# MultiDrop.net
KiCad netlist of a schematic drawn in EAGLE
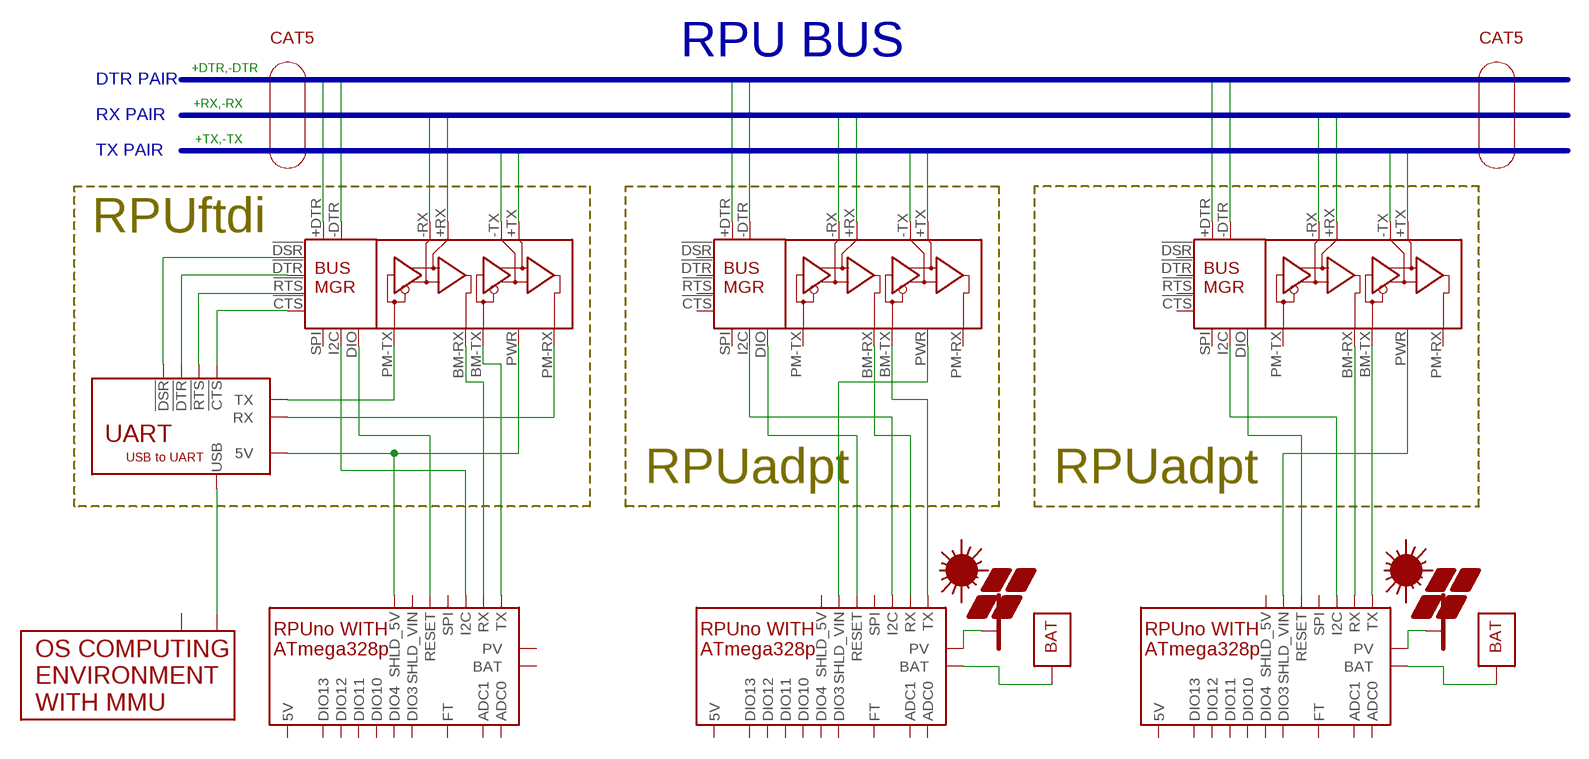
[diagram p0: schematic, sheet 1]

(export (version "E")
  (design (tool "Eeschema 10.0.6"))
  (components
    (comp (ref "BM1")
      (value "RPUNO")
      (footprint "eagle-import:NA-20")
      (libsource (lib "eagle-import") (part "RPUNO"))
    )
    (comp (ref "BM2")
      (value "RPUNO")
      (footprint "eagle-import:NA-20")
      (libsource (lib "eagle-import") (part "RPUNO"))
    )
    (comp (ref "BM3")
      (value "RPUNO")
      (footprint "eagle-import:NA-20")
      (libsource (lib "eagle-import") (part "RPUNO"))
    )
    (comp (ref "PM2")
      (value "TRUSTWORTHY")
      (footprint "eagle-import:NA-20")
      (libsource (lib "eagle-import") (part "TRUSTWORTHY"))
    )
    (comp (ref "PV2")
      (value "PV")
      (footprint "eagle-import:NA-20")
      (libsource (lib "eagle-import") (part "PV"))
    )
    (comp (ref "PV4")
      (value "PV")
      (footprint "eagle-import:NA-20")
      (libsource (lib "eagle-import") (part "PV"))
    )
    (comp (ref "U$1")
      (value "BUS_MGR")
      (footprint "eagle-import:NA-10_WITH_RPU_NAMES")
      (libsource (lib "eagle-import") (part "BUS_MGR"))
    )
    (comp (ref "U$2")
      (value "BUS_MGR")
      (footprint "eagle-import:NA-10_WITH_RPU_NAMES")
      (libsource (lib "eagle-import") (part "BUS_MGR"))
    )
    (comp (ref "U$5")
      (value "BUS_MGR")
      (footprint "eagle-import:NA-10_WITH_RPU_NAMES")
      (libsource (lib "eagle-import") (part "BUS_MGR"))
    )
    (comp (ref "U$7")
      (value "BAT")
      (footprint "eagle-import:NA-20")
      (libsource (lib "eagle-import") (part "BAT"))
    )
    (comp (ref "U$9")
      (value "BAT")
      (footprint "eagle-import:NA-20")
      (libsource (lib "eagle-import") (part "BAT"))
    )
    (comp (ref "UART1")
      (value "UART")
      (footprint "eagle-import:NA-20")
      (libsource (lib "eagle-import") (part "UART"))
    )
  )
  (nets
    (net (code "10") (name "Net-(BM1-BAT)") (class "Default")
      (node (ref "BM1") (pin "9") (pinfunction "BAT_9") (pintype "bidirectional"))
      (node (ref "U$9") (pin "1") (pinfunction "BAT_PWR_1") (pintype "bidirectional"))
    )
    (net (code "11") (name "Net-(BM1-I2C)") (class "Default")
      (node (ref "BM1") (pin "3") (pinfunction "I2C_3") (pintype "bidirectional"))
      (node (ref "U$2") (pin "I2C") (pinfunction "I2C_I2C") (pintype "bidirectional"))
    )
    (net (code "12") (name "Net-(BM1-PV)") (class "Default")
      (node (ref "BM1") (pin "8") (pinfunction "PV_8") (pintype "bidirectional"))
      (node (ref "PV2") (pin "1") (pinfunction "PV_PWR_1") (pintype "bidirectional"))
    )
    (net (code "13") (name "Net-(BM1-RESET)") (class "Default")
      (node (ref "BM1") (pin "5") (pinfunction "RESET_5") (pintype "bidirectional"))
      (node (ref "U$2") (pin "DIO") (pinfunction "DIO_DIO") (pintype "bidirectional"))
    )
    (net (code "14") (name "Net-(BM1-RX)") (class "Default")
      (node (ref "BM1") (pin "2") (pinfunction "RX_2") (pintype "bidirectional"))
      (node (ref "U$2") (pin "BM-RX") (pinfunction "BM_RX_BM-RX") (pintype "bidirectional"))
    )
    (net (code "15") (name "Net-(BM1-SHLD_VIN)") (class "Default")
      (node (ref "BM1") (pin "7") (pinfunction "SHLD_VIN_7") (pintype "bidirectional"))
      (node (ref "U$2") (pin "PWR") (pinfunction "PWR_PWR") (pintype "bidirectional"))
    )
    (net (code "16") (name "Net-(BM1-TX)") (class "Default")
      (node (ref "BM1") (pin "1") (pinfunction "TX_1") (pintype "bidirectional"))
      (node (ref "U$2") (pin "BM-TX") (pinfunction "BM_TX_BM-TX") (pintype "bidirectional"))
    )
    (net (code "17") (name "Net-(BM2-I2C)") (class "Default")
      (node (ref "BM2") (pin "3") (pinfunction "I2C_3") (pintype "bidirectional"))
      (node (ref "U$1") (pin "I2C") (pinfunction "I2C_I2C") (pintype "bidirectional"))
    )
    (net (code "18") (name "Net-(BM2-RESET)") (class "Default")
      (node (ref "BM2") (pin "5") (pinfunction "RESET_5") (pintype "bidirectional"))
      (node (ref "U$1") (pin "DIO") (pinfunction "DIO_DIO") (pintype "bidirectional"))
    )
    (net (code "19") (name "Net-(BM2-RX)") (class "Default")
      (node (ref "BM2") (pin "2") (pinfunction "RX_2") (pintype "bidirectional"))
      (node (ref "U$1") (pin "BM-RX") (pinfunction "BM_RX_BM-RX") (pintype "bidirectional"))
    )
    (net (code "20") (name "Net-(BM2-SHLD_5V)") (class "Default")
      (node (ref "BM2") (pin "6") (pinfunction "SHLD_5V_6") (pintype "bidirectional"))
      (node (ref "U$1") (pin "PWR") (pinfunction "PWR_PWR") (pintype "bidirectional"))
      (node (ref "UART1") (pin "8") (pinfunction "5V_8") (pintype "bidirectional"))
    )
    (net (code "21") (name "Net-(BM2-TX)") (class "Default")
      (node (ref "BM2") (pin "1") (pinfunction "TX_1") (pintype "bidirectional"))
      (node (ref "U$1") (pin "BM-TX") (pinfunction "BM_TX_BM-TX") (pintype "bidirectional"))
    )
    (net (code "22") (name "Net-(BM3-BAT)") (class "Default")
      (node (ref "BM3") (pin "9") (pinfunction "BAT_9") (pintype "bidirectional"))
      (node (ref "U$7") (pin "1") (pinfunction "BAT_PWR_1") (pintype "bidirectional"))
    )
    (net (code "23") (name "Net-(BM3-I2C)") (class "Default")
      (node (ref "BM3") (pin "3") (pinfunction "I2C_3") (pintype "bidirectional"))
      (node (ref "U$5") (pin "I2C") (pinfunction "I2C_I2C") (pintype "bidirectional"))
    )
    (net (code "24") (name "Net-(BM3-PV)") (class "Default")
      (node (ref "BM3") (pin "8") (pinfunction "PV_8") (pintype "bidirectional"))
      (node (ref "PV4") (pin "1") (pinfunction "PV_PWR_1") (pintype "bidirectional"))
    )
    (net (code "25") (name "Net-(BM3-RESET)") (class "Default")
      (node (ref "BM3") (pin "5") (pinfunction "RESET_5") (pintype "bidirectional"))
      (node (ref "U$5") (pin "DIO") (pinfunction "DIO_DIO") (pintype "bidirectional"))
    )
    (net (code "26") (name "Net-(BM3-RX)") (class "Default")
      (node (ref "BM3") (pin "2") (pinfunction "RX_2") (pintype "bidirectional"))
      (node (ref "U$5") (pin "BM-RX") (pinfunction "BM_RX_BM-RX") (pintype "bidirectional"))
    )
    (net (code "27") (name "Net-(BM3-SHLD_VIN)") (class "Default")
      (node (ref "BM3") (pin "7") (pinfunction "SHLD_VIN_7") (pintype "bidirectional"))
      (node (ref "U$5") (pin "PWR") (pinfunction "PWR_PWR") (pintype "bidirectional"))
    )
    (net (code "28") (name "Net-(BM3-TX)") (class "Default")
      (node (ref "BM3") (pin "1") (pinfunction "TX_1") (pintype "bidirectional"))
      (node (ref "U$5") (pin "BM-TX") (pinfunction "BM_TX_BM-TX") (pintype "bidirectional"))
    )
    (net (code "29") (name "Net-(PM2-TX)") (class "Default")
      (node (ref "PM2") (pin "2") (pinfunction "TX_2") (pintype "bidirectional"))
      (node (ref "UART1") (pin "7") (pinfunction "USB_7") (pintype "bidirectional"))
    )
    (net (code "30") (name "Net-(U$1-PM_RX)") (class "Default")
      (node (ref "U$1") (pin "PM-RX") (pinfunction "PM_RX_PM-RX") (pintype "bidirectional"))
      (node (ref "UART1") (pin "5") (pinfunction "RX_5") (pintype "bidirectional"))
    )
    (net (code "31") (name "Net-(U$1-PM_TX)") (class "Default")
      (node (ref "U$1") (pin "PM-TX") (pinfunction "PM_TX_PM-TX") (pintype "bidirectional"))
      (node (ref "UART1") (pin "6") (pinfunction "TX_6") (pintype "bidirectional"))
    )
    (net (code "32") (name "Net-(U$1-~{CTS})") (class "Default")
      (node (ref "U$1") (pin "!CTS") (pinfunction "~{CTS}_!CTS") (pintype "bidirectional"))
      (node (ref "UART1") (pin "1") (pinfunction "~{CTS}_1") (pintype "input"))
    )
    (net (code "33") (name "Net-(U$1-~{DSR})") (class "Default")
      (node (ref "U$1") (pin "!DSR") (pinfunction "~{DSR}_!DSR") (pintype "bidirectional"))
      (node (ref "UART1") (pin "2") (pinfunction "~{DSR}_2") (pintype "input"))
    )
    (net (code "34") (name "Net-(U$1-~{DTR})") (class "Default")
      (node (ref "U$1") (pin "!DTR") (pinfunction "~{DTR}_!DTR") (pintype "bidirectional"))
      (node (ref "UART1") (pin "3") (pinfunction "~{DTR}_3") (pintype "output"))
    )
    (net (code "35") (name "Net-(U$1-~{RTS})") (class "Default")
      (node (ref "U$1") (pin "!RTS") (pinfunction "~{RTS}_!RTS") (pintype "bidirectional"))
      (node (ref "UART1") (pin "4") (pinfunction "~{RTS}_4") (pintype "output"))
    )
    (net (code "36") (name "unconnected-(BM1-5V-Pad19)") (class "Default")
      (node (ref "BM1") (pin "19") (pinfunction "5V_19") (pintype "bidirectional"))
    )
    (net (code "37") (name "unconnected-(BM1-ADC0-Pad10)") (class "Default")
      (node (ref "BM1") (pin "10") (pinfunction "ADC0_10") (pintype "bidirectional"))
    )
    (net (code "38") (name "unconnected-(BM1-ADC1-Pad11)") (class "Default")
      (node (ref "BM1") (pin "11") (pinfunction "ADC1_11") (pintype "bidirectional"))
    )
    (net (code "39") (name "unconnected-(BM1-DIO3-Pad13)") (class "Default")
      (node (ref "BM1") (pin "13") (pinfunction "DIO3_13") (pintype "bidirectional"))
    )
    (net (code "40") (name "unconnected-(BM1-DIO4-Pad14)") (class "Default")
      (node (ref "BM1") (pin "14") (pinfunction "DIO4_14") (pintype "bidirectional"))
    )
    (net (code "41") (name "unconnected-(BM1-DIO10-Pad15)") (class "Default")
      (node (ref "BM1") (pin "15") (pinfunction "DIO10_15") (pintype "bidirectional"))
    )
    (net (code "42") (name "unconnected-(BM1-DIO11-Pad16)") (class "Default")
      (node (ref "BM1") (pin "16") (pinfunction "DIO11_16") (pintype "bidirectional"))
    )
    (net (code "43") (name "unconnected-(BM1-DIO12-Pad17)") (class "Default")
      (node (ref "BM1") (pin "17") (pinfunction "DIO12_17") (pintype "bidirectional"))
    )
    (net (code "44") (name "unconnected-(BM1-DIO13-Pad18)") (class "Default")
      (node (ref "BM1") (pin "18") (pinfunction "DIO13_18") (pintype "bidirectional"))
    )
    (net (code "45") (name "unconnected-(BM1-FT-Pad12)") (class "Default")
      (node (ref "BM1") (pin "12") (pinfunction "FT_12") (pintype "bidirectional"))
    )
    (net (code "46") (name "unconnected-(BM1-SHLD_5V-Pad6)") (class "Default")
      (node (ref "BM1") (pin "6") (pinfunction "SHLD_5V_6") (pintype "bidirectional"))
    )
    (net (code "47") (name "unconnected-(BM1-SPI-Pad4)") (class "Default")
      (node (ref "BM1") (pin "4") (pinfunction "SPI_4") (pintype "bidirectional"))
    )
    (net (code "48") (name "unconnected-(BM2-5V-Pad19)") (class "Default")
      (node (ref "BM2") (pin "19") (pinfunction "5V_19") (pintype "bidirectional"))
    )
    (net (code "49") (name "unconnected-(BM2-ADC0-Pad10)") (class "Default")
      (node (ref "BM2") (pin "10") (pinfunction "ADC0_10") (pintype "bidirectional"))
    )
    (net (code "50") (name "unconnected-(BM2-ADC1-Pad11)") (class "Default")
      (node (ref "BM2") (pin "11") (pinfunction "ADC1_11") (pintype "bidirectional"))
    )
    (net (code "51") (name "unconnected-(BM2-BAT-Pad9)") (class "Default")
      (node (ref "BM2") (pin "9") (pinfunction "BAT_9") (pintype "bidirectional"))
    )
    (net (code "52") (name "unconnected-(BM2-DIO3-Pad13)") (class "Default")
      (node (ref "BM2") (pin "13") (pinfunction "DIO3_13") (pintype "bidirectional"))
    )
    (net (code "53") (name "unconnected-(BM2-DIO4-Pad14)") (class "Default")
      (node (ref "BM2") (pin "14") (pinfunction "DIO4_14") (pintype "bidirectional"))
    )
    (net (code "54") (name "unconnected-(BM2-DIO10-Pad15)") (class "Default")
      (node (ref "BM2") (pin "15") (pinfunction "DIO10_15") (pintype "bidirectional"))
    )
    (net (code "55") (name "unconnected-(BM2-DIO11-Pad16)") (class "Default")
      (node (ref "BM2") (pin "16") (pinfunction "DIO11_16") (pintype "bidirectional"))
    )
    (net (code "56") (name "unconnected-(BM2-DIO12-Pad17)") (class "Default")
      (node (ref "BM2") (pin "17") (pinfunction "DIO12_17") (pintype "bidirectional"))
    )
    (net (code "57") (name "unconnected-(BM2-DIO13-Pad18)") (class "Default")
      (node (ref "BM2") (pin "18") (pinfunction "DIO13_18") (pintype "bidirectional"))
    )
    (net (code "58") (name "unconnected-(BM2-FT-Pad12)") (class "Default")
      (node (ref "BM2") (pin "12") (pinfunction "FT_12") (pintype "bidirectional"))
    )
    (net (code "59") (name "unconnected-(BM2-PV-Pad8)") (class "Default")
      (node (ref "BM2") (pin "8") (pinfunction "PV_8") (pintype "bidirectional"))
    )
    (net (code "60") (name "unconnected-(BM2-SHLD_VIN-Pad7)") (class "Default")
      (node (ref "BM2") (pin "7") (pinfunction "SHLD_VIN_7") (pintype "bidirectional"))
    )
    (net (code "61") (name "unconnected-(BM2-SPI-Pad4)") (class "Default")
      (node (ref "BM2") (pin "4") (pinfunction "SPI_4") (pintype "bidirectional"))
    )
    (net (code "62") (name "unconnected-(BM3-5V-Pad19)") (class "Default")
      (node (ref "BM3") (pin "19") (pinfunction "5V_19") (pintype "bidirectional"))
    )
    (net (code "63") (name "unconnected-(BM3-ADC0-Pad10)") (class "Default")
      (node (ref "BM3") (pin "10") (pinfunction "ADC0_10") (pintype "bidirectional"))
    )
    (net (code "64") (name "unconnected-(BM3-ADC1-Pad11)") (class "Default")
      (node (ref "BM3") (pin "11") (pinfunction "ADC1_11") (pintype "bidirectional"))
    )
    (net (code "65") (name "unconnected-(BM3-DIO3-Pad13)") (class "Default")
      (node (ref "BM3") (pin "13") (pinfunction "DIO3_13") (pintype "bidirectional"))
    )
    (net (code "66") (name "unconnected-(BM3-DIO4-Pad14)") (class "Default")
      (node (ref "BM3") (pin "14") (pinfunction "DIO4_14") (pintype "bidirectional"))
    )
    (net (code "67") (name "unconnected-(BM3-DIO10-Pad15)") (class "Default")
      (node (ref "BM3") (pin "15") (pinfunction "DIO10_15") (pintype "bidirectional"))
    )
    (net (code "68") (name "unconnected-(BM3-DIO11-Pad16)") (class "Default")
      (node (ref "BM3") (pin "16") (pinfunction "DIO11_16") (pintype "bidirectional"))
    )
    (net (code "69") (name "unconnected-(BM3-DIO12-Pad17)") (class "Default")
      (node (ref "BM3") (pin "17") (pinfunction "DIO12_17") (pintype "bidirectional"))
    )
    (net (code "70") (name "unconnected-(BM3-DIO13-Pad18)") (class "Default")
      (node (ref "BM3") (pin "18") (pinfunction "DIO13_18") (pintype "bidirectional"))
    )
    (net (code "71") (name "unconnected-(BM3-FT-Pad12)") (class "Default")
      (node (ref "BM3") (pin "12") (pinfunction "FT_12") (pintype "bidirectional"))
    )
    (net (code "72") (name "unconnected-(BM3-SHLD_5V-Pad6)") (class "Default")
      (node (ref "BM3") (pin "6") (pinfunction "SHLD_5V_6") (pintype "bidirectional"))
    )
    (net (code "73") (name "unconnected-(BM3-SPI-Pad4)") (class "Default")
      (node (ref "BM3") (pin "4") (pinfunction "SPI_4") (pintype "bidirectional"))
    )
    (net (code "74") (name "unconnected-(PM2-RX-Pad1)") (class "Default")
      (node (ref "PM2") (pin "1") (pinfunction "RX_1") (pintype "bidirectional"))
    )
    (net (code "75") (name "unconnected-(U$1-Pad+DTR)") (class "Default")
      (node (ref "U$1") (pin "+DTR") (pinfunction "+DTR_+DTR") (pintype "bidirectional"))
    )
    (net (code "76") (name "unconnected-(U$1-Pad+RX)") (class "Default")
      (node (ref "U$1") (pin "+RX") (pinfunction "+RX_+RX") (pintype "bidirectional"))
    )
    (net (code "77") (name "unconnected-(U$1-Pad+TX)") (class "Default")
      (node (ref "U$1") (pin "+TX") (pinfunction "+TX_+TX") (pintype "bidirectional"))
    )
    (net (code "78") (name "unconnected-(U$1-Pad-DTR)") (class "Default")
      (node (ref "U$1") (pin "-DTR") (pinfunction "-DTR_-DTR") (pintype "bidirectional"))
    )
    (net (code "79") (name "unconnected-(U$1-Pad-RX)") (class "Default")
      (node (ref "U$1") (pin "-RX") (pinfunction "-RX_-RX") (pintype "bidirectional"))
    )
    (net (code "80") (name "unconnected-(U$1-Pad-TX)") (class "Default")
      (node (ref "U$1") (pin "-TX") (pinfunction "-TX_-TX") (pintype "bidirectional"))
    )
    (net (code "81") (name "unconnected-(U$1-PadSPI)") (class "Default")
      (node (ref "U$1") (pin "SPI") (pinfunction "SPI_SPI") (pintype "bidirectional"))
    )
    (net (code "82") (name "unconnected-(U$2-PM_RX-PadPM-RX)") (class "Default")
      (node (ref "U$2") (pin "PM-RX") (pinfunction "PM_RX_PM-RX") (pintype "bidirectional"))
    )
    (net (code "83") (name "unconnected-(U$2-PM_TX-PadPM-TX)") (class "Default")
      (node (ref "U$2") (pin "PM-TX") (pinfunction "PM_TX_PM-TX") (pintype "bidirectional"))
    )
    (net (code "84") (name "unconnected-(U$2-Pad+DTR)") (class "Default")
      (node (ref "U$2") (pin "+DTR") (pinfunction "+DTR_+DTR") (pintype "bidirectional"))
    )
    (net (code "85") (name "unconnected-(U$2-Pad+RX)") (class "Default")
      (node (ref "U$2") (pin "+RX") (pinfunction "+RX_+RX") (pintype "bidirectional"))
    )
    (net (code "86") (name "unconnected-(U$2-Pad+TX)") (class "Default")
      (node (ref "U$2") (pin "+TX") (pinfunction "+TX_+TX") (pintype "bidirectional"))
    )
    (net (code "87") (name "unconnected-(U$2-Pad-DTR)") (class "Default")
      (node (ref "U$2") (pin "-DTR") (pinfunction "-DTR_-DTR") (pintype "bidirectional"))
    )
    (net (code "88") (name "unconnected-(U$2-Pad-RX)") (class "Default")
      (node (ref "U$2") (pin "-RX") (pinfunction "-RX_-RX") (pintype "bidirectional"))
    )
    (net (code "89") (name "unconnected-(U$2-Pad-TX)") (class "Default")
      (node (ref "U$2") (pin "-TX") (pinfunction "-TX_-TX") (pintype "bidirectional"))
    )
    (net (code "90") (name "unconnected-(U$2-PadSPI)") (class "Default")
      (node (ref "U$2") (pin "SPI") (pinfunction "SPI_SPI") (pintype "bidirectional"))
    )
    (net (code "91") (name "unconnected-(U$2-~{CTS}-Pad!CTS)") (class "Default")
      (node (ref "U$2") (pin "!CTS") (pinfunction "~{CTS}_!CTS") (pintype "bidirectional"))
    )
    (net (code "92") (name "unconnected-(U$2-~{DSR}-Pad!DSR)") (class "Default")
      (node (ref "U$2") (pin "!DSR") (pinfunction "~{DSR}_!DSR") (pintype "bidirectional"))
    )
    (net (code "93") (name "unconnected-(U$2-~{DTR}-Pad!DTR)") (class "Default")
      (node (ref "U$2") (pin "!DTR") (pinfunction "~{DTR}_!DTR") (pintype "bidirectional"))
    )
    (net (code "94") (name "unconnected-(U$2-~{RTS}-Pad!RTS)") (class "Default")
      (node (ref "U$2") (pin "!RTS") (pinfunction "~{RTS}_!RTS") (pintype "bidirectional"))
    )
    (net (code "95") (name "unconnected-(U$5-PM_RX-PadPM-RX)") (class "Default")
      (node (ref "U$5") (pin "PM-RX") (pinfunction "PM_RX_PM-RX") (pintype "bidirectional"))
    )
    (net (code "96") (name "unconnected-(U$5-PM_TX-PadPM-TX)") (class "Default")
      (node (ref "U$5") (pin "PM-TX") (pinfunction "PM_TX_PM-TX") (pintype "bidirectional"))
    )
    (net (code "97") (name "unconnected-(U$5-Pad+DTR)") (class "Default")
      (node (ref "U$5") (pin "+DTR") (pinfunction "+DTR_+DTR") (pintype "bidirectional"))
    )
    (net (code "98") (name "unconnected-(U$5-Pad+RX)") (class "Default")
      (node (ref "U$5") (pin "+RX") (pinfunction "+RX_+RX") (pintype "bidirectional"))
    )
    (net (code "99") (name "unconnected-(U$5-Pad+TX)") (class "Default")
      (node (ref "U$5") (pin "+TX") (pinfunction "+TX_+TX") (pintype "bidirectional"))
    )
    (net (code "100") (name "unconnected-(U$5-Pad-DTR)") (class "Default")
      (node (ref "U$5") (pin "-DTR") (pinfunction "-DTR_-DTR") (pintype "bidirectional"))
    )
    (net (code "101") (name "unconnected-(U$5-Pad-RX)") (class "Default")
      (node (ref "U$5") (pin "-RX") (pinfunction "-RX_-RX") (pintype "bidirectional"))
    )
    (net (code "102") (name "unconnected-(U$5-Pad-TX)") (class "Default")
      (node (ref "U$5") (pin "-TX") (pinfunction "-TX_-TX") (pintype "bidirectional"))
    )
    (net (code "103") (name "unconnected-(U$5-PadSPI)") (class "Default")
      (node (ref "U$5") (pin "SPI") (pinfunction "SPI_SPI") (pintype "bidirectional"))
    )
    (net (code "104") (name "unconnected-(U$5-~{CTS}-Pad!CTS)") (class "Default")
      (node (ref "U$5") (pin "!CTS") (pinfunction "~{CTS}_!CTS") (pintype "bidirectional"))
    )
    (net (code "105") (name "unconnected-(U$5-~{DSR}-Pad!DSR)") (class "Default")
      (node (ref "U$5") (pin "!DSR") (pinfunction "~{DSR}_!DSR") (pintype "bidirectional"))
    )
    (net (code "106") (name "unconnected-(U$5-~{DTR}-Pad!DTR)") (class "Default")
      (node (ref "U$5") (pin "!DTR") (pinfunction "~{DTR}_!DTR") (pintype "bidirectional"))
    )
    (net (code "107") (name "unconnected-(U$5-~{RTS}-Pad!RTS)") (class "Default")
      (node (ref "U$5") (pin "!RTS") (pinfunction "~{RTS}_!RTS") (pintype "bidirectional"))
    )
  )
)
